# ESP32.net
KiCad netlist of a schematic drawn in Altium Designer
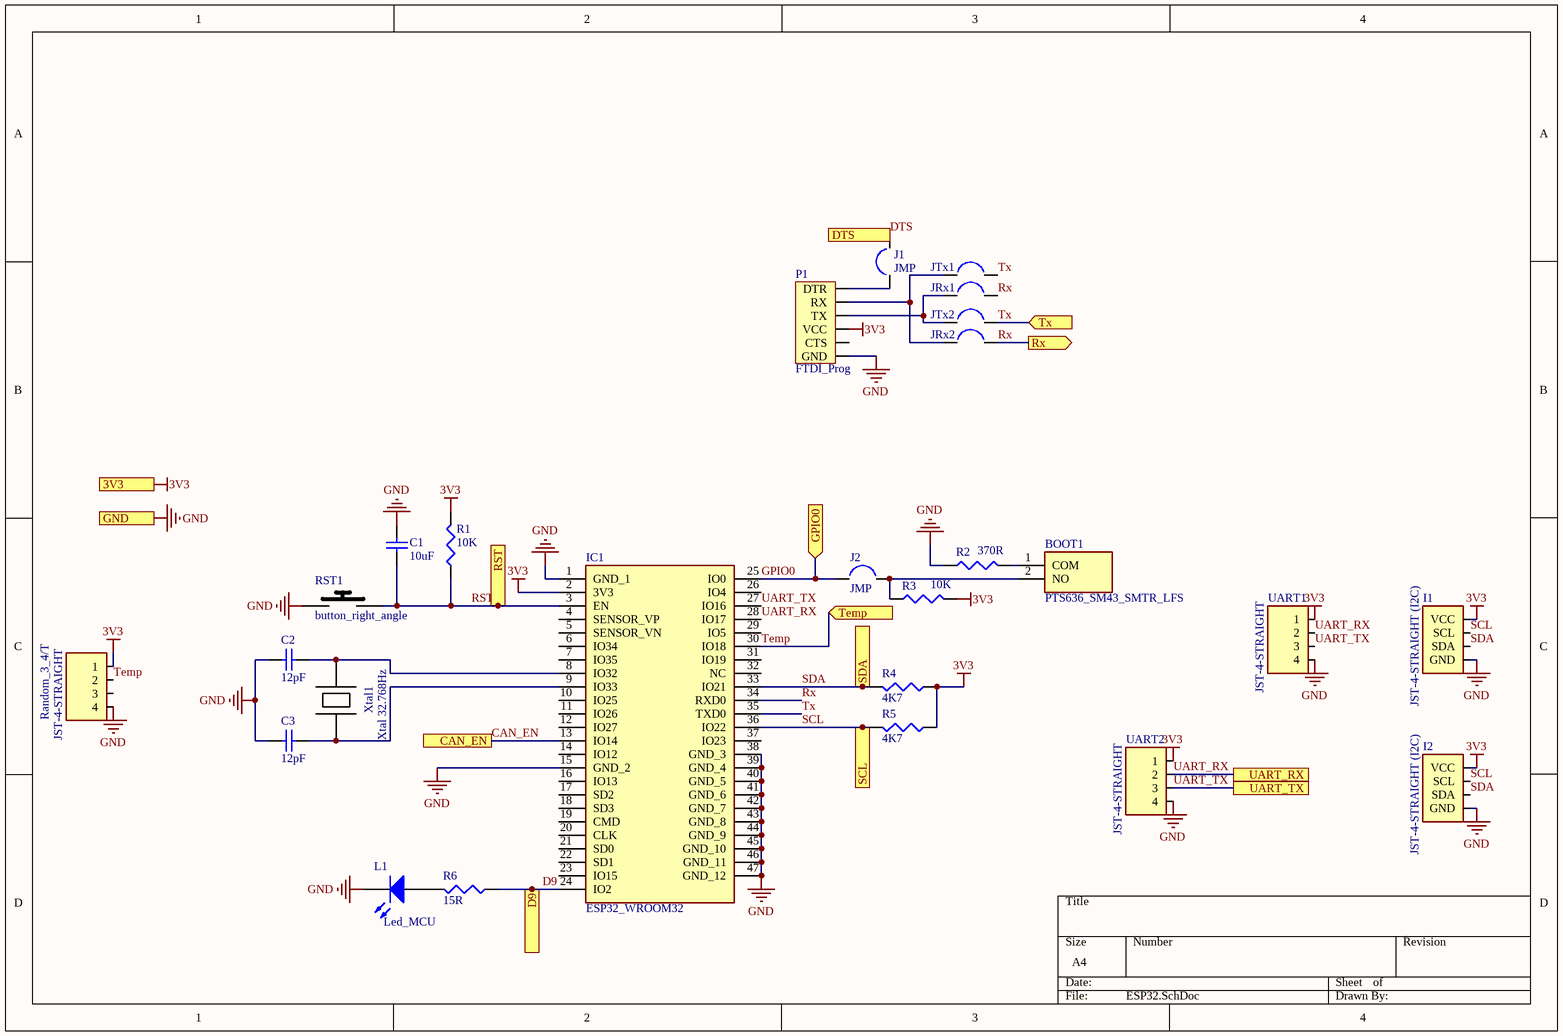
[diagram p0: ESP32.SchDoc]

(export (version "E")
  (design (tool "Eeschema 10.0.6"))
  (components
    (comp (ref "BOOT1")
      (value "PTS636_SM43_SMTR_LFS")
      (footprint "SamacSys:PTS636SM43SMTRLFS")
      (description "Switch")
      (fields
        (field (name "MANUFACTURER_PART_NUMBER") "PTS636 SM43 SMTR LFS")
        (field (name "MOUSER PART NUMBER") "611-PTS636SM43SMTRLF")
      )
      (libsource (lib "*") (part "PTS636_SM43_SMTR_LFS"))
    )
    (comp (ref "C1")
      (value "10uF")
      (footprint "1608[0603]")
      (description "Capacitor (Semiconductor SIM Model)")
      (fields (field (name "PUBLISHER") "Altium Limited"))
      (libsource (lib "Miscellaneous Devices") (part "Cap Semi"))
    )
    (comp (ref "C2")
      (value "12pF")
      (footprint "1608[0603]")
      (description "Capacitor (Semiconductor SIM Model)")
      (fields (field (name "PUBLISHER") "Altium Limited"))
      (libsource (lib "Miscellaneous Devices") (part "Cap Semi"))
    )
    (comp (ref "C3")
      (value "12pF")
      (footprint "1608[0603]")
      (description "Capacitor (Semiconductor SIM Model)")
      (fields (field (name "PUBLISHER") "Altium Limited"))
      (libsource (lib "Miscellaneous Devices") (part "Cap Semi"))
    )
    (comp (ref "I1")
      (value "JST-4-STRAIGHT (I2C)")
      (footprint "JST-4-STRAIGHT")
      (libsource (lib "SamacSys") (part "JST-4-STRAIGHT (I2C)"))
    )
    (comp (ref "I2")
      (value "JST-4-STRAIGHT (I2C)")
      (footprint "JST-4-STRAIGHT")
      (libsource (lib "SamacSys") (part "JST-4-STRAIGHT (I2C)"))
    )
    (comp (ref "IC1")
      (value "ESP32_WROOM32")
      (footprint "SamacSys:ESP32WROOM32")
      (description "Integrated Circuit")
      (fields (field (name "MANUFACTURER_PART_NUMBER") "ESP32 WROOM32"))
      (libsource (lib "SamacSys") (part "ESP32_WROOM32"))
    )
    (comp (ref "J1") (value "JMP") (footprint "Jumper") (libsource (lib "SamacSys") (part "JMP")))
    (comp (ref "J2") (value "JMP") (footprint "Jumper") (libsource (lib "SamacSys") (part "JMP")))
    (comp (ref "JRx1") (value "JMP") (footprint "Jumper") (libsource (lib "SamacSys") (part "JMP")))
    (comp (ref "JRx2") (value "JMP") (footprint "Jumper") (libsource (lib "SamacSys") (part "JMP")))
    (comp (ref "JTx1") (value "JMP") (footprint "Jumper") (libsource (lib "SamacSys") (part "JMP")))
    (comp (ref "JTx2") (value "JMP") (footprint "Jumper") (libsource (lib "SamacSys") (part "JMP")))
    (comp (ref "L1")
      (value "Led_MCU")
      (footprint "LED 0603")
      (description "Typical BLUE SiC LED")
      (fields (field (name "PUBLISHER") "Altium Limited"))
      (libsource (lib "Miscellaneous Devices") (part "LED3"))
    )
    (comp (ref "P1")
      (value "FTDI_Prog")
      (footprint "programer")
      (description "FTDI_programer FT232RL USB TO TTL")
      (libsource (lib "SamacSys") (part "Programer"))
    )
    (comp (ref "R1")
      (value "10K")
      (footprint "J1-0603")
      (description "Resistor")
      (fields (field (name "PUBLISHER") "Altium Limited"))
      (libsource (lib "Miscellaneous Devices") (part "Res3"))
    )
    (comp (ref "R2")
      (value "370R")
      (footprint "J1-0603")
      (description "Resistor")
      (fields (field (name "PUBLISHER") "Altium Limited"))
      (libsource (lib "Miscellaneous Devices") (part "Res3"))
    )
    (comp (ref "R3")
      (value "10K")
      (footprint "J1-0603")
      (description "Resistor")
      (fields (field (name "PUBLISHER") "Altium Limited"))
      (libsource (lib "Miscellaneous Devices") (part "Res3"))
    )
    (comp (ref "R4")
      (value "4K7")
      (footprint "J1-0603")
      (description "Resistor")
      (fields (field (name "PUBLISHER") "Altium Limited"))
      (libsource (lib "Miscellaneous Devices") (part "Res3"))
    )
    (comp (ref "R5")
      (value "4K7")
      (footprint "J1-0603")
      (description "Resistor")
      (fields (field (name "PUBLISHER") "Altium Limited"))
      (libsource (lib "Miscellaneous Devices") (part "Res3"))
    )
    (comp (ref "R6")
      (value "15R")
      (footprint "J1-0603")
      (description "Resistor")
      (fields (field (name "PUBLISHER") "Altium Limited"))
      (libsource (lib "Miscellaneous Devices") (part "Res3"))
    )
    (comp (ref "Random_3_4/T")
      (value "JST-4-STRAIGHT")
      (footprint "JST-4-STRAIGHT")
      (libsource (lib "SamacSys") (part "JST-4-STRAIGHT"))
    )
    (comp (ref "RST1")
      (value "button_right_angle")
      (footprint "1825027-8")
      (description "Switch")
      (fields
        (field (name "MANUFACTURER_PART_NUMBER") "1825027-8")
        (field (name "MOUSER PART NUMBER") "506-1825027-8")
      )
      (libsource (lib "SamacSys") (part "button_right_angle"))
    )
    (comp (ref "UART1")
      (value "JST-4-STRAIGHT")
      (footprint "JST-4-STRAIGHT")
      (libsource (lib "SamacSys") (part "JST-4-STRAIGHT"))
    )
    (comp (ref "UART2")
      (value "JST-4-STRAIGHT")
      (footprint "JST-4-STRAIGHT")
      (libsource (lib "SamacSys") (part "JST-4-STRAIGHT"))
    )
    (comp (ref "Xtal1")
      (value "Xtal 32.768Hz")
      (footprint "LFXTAL050789")
      (description "32.7680kHz")
      (libsource (lib "SamacSys") (part "Crystals WE-XTAL 32.7680kHz"))
    )
  )
  (nets
    (net (code "1") (name "/CAN_EN") (class "Default")
      (node (ref "IC1") (pin "13") (pinfunction "IO14_13") (pintype "passive"))
    )
    (net (code "2") (name "/D9") (class "Default")
      (node (ref "IC1") (pin "24") (pinfunction "IO2_24") (pintype "passive"))
      (node (ref "R6") (pin "1") (pinfunction "1_1") (pintype "passive"))
    )
    (net (code "3") (name "/DTS") (class "Default")
      (node (ref "J1") (pin "2") (pinfunction "2_2") (pintype "passive"))
    )
    (net (code "4") (name "/GPIO0") (class "Default")
      (node (ref "IC1") (pin "25") (pinfunction "IO0_25") (pintype "passive"))
      (node (ref "J2") (pin "1") (pinfunction "1_1") (pintype "passive"))
    )
    (net (code "5") (name "/RST") (class "Default")
      (node (ref "C1") (pin "1") (pinfunction "1_1") (pintype "passive"))
      (node (ref "IC1") (pin "3") (pinfunction "EN_3") (pintype "passive"))
      (node (ref "R1") (pin "1") (pinfunction "1_1") (pintype "passive"))
      (node (ref "RST1") (pin "2") (pinfunction "2_2") (pintype "passive"))
    )
    (net (code "6") (name "/Rx") (class "Default")
      (node (ref "IC1") (pin "34") (pinfunction "RXD0_34") (pintype "passive"))
      (node (ref "JRx1") (pin "2") (pinfunction "2_2") (pintype "passive"))
      (node (ref "JRx2") (pin "2") (pinfunction "2_2") (pintype "passive"))
    )
    (net (code "7") (name "/SCL") (class "Default")
      (node (ref "I1") (pin "2") (pinfunction "SCL_2") (pintype "passive"))
      (node (ref "I2") (pin "2") (pinfunction "SCL_2") (pintype "passive"))
      (node (ref "IC1") (pin "36") (pinfunction "IO22_36") (pintype "passive"))
      (node (ref "R5") (pin "2") (pinfunction "2_2") (pintype "passive"))
    )
    (net (code "8") (name "/SDA") (class "Default")
      (node (ref "I1") (pin "3") (pinfunction "SDA_3") (pintype "passive"))
      (node (ref "I2") (pin "3") (pinfunction "SDA_3") (pintype "passive"))
      (node (ref "IC1") (pin "33") (pinfunction "IO21_33") (pintype "passive"))
      (node (ref "R4") (pin "2") (pinfunction "2_2") (pintype "passive"))
    )
    (net (code "9") (name "/Temp") (class "Default")
      (node (ref "IC1") (pin "30") (pinfunction "IO18_30") (pintype "passive"))
      (node (ref "Random_3_4/T") (pin "2") (pinfunction "2_2") (pintype "passive"))
    )
    (net (code "10") (name "/Tx") (class "Default")
      (node (ref "IC1") (pin "35") (pinfunction "TXD0_35") (pintype "passive"))
      (node (ref "JTx1") (pin "2") (pinfunction "2_2") (pintype "passive"))
      (node (ref "JTx2") (pin "2") (pinfunction "2_2") (pintype "passive"))
    )
    (net (code "11") (name "/UART_RX") (class "Default")
      (node (ref "IC1") (pin "28") (pinfunction "IO17_28") (pintype "passive"))
      (node (ref "UART1") (pin "2") (pinfunction "2_2") (pintype "passive"))
      (node (ref "UART2") (pin "2") (pinfunction "2_2") (pintype "passive"))
    )
    (net (code "12") (name "/UART_TX") (class "Default")
      (node (ref "IC1") (pin "27") (pinfunction "IO16_27") (pintype "passive"))
      (node (ref "UART1") (pin "3") (pinfunction "3_3") (pintype "passive"))
      (node (ref "UART2") (pin "3") (pinfunction "3_3") (pintype "passive"))
    )
    (net (code "13") (name "3V3") (class "Default")
      (node (ref "I1") (pin "1") (pinfunction "VCC_1") (pintype "passive"))
      (node (ref "I2") (pin "1") (pinfunction "VCC_1") (pintype "passive"))
      (node (ref "IC1") (pin "2") (pinfunction "3V3_2") (pintype "passive"))
      (node (ref "P1") (pin "4") (pinfunction "VCC_4") (pintype "passive"))
      (node (ref "R1") (pin "2") (pinfunction "2_2") (pintype "passive"))
      (node (ref "R3") (pin "2") (pinfunction "2_2") (pintype "passive"))
      (node (ref "R4") (pin "1") (pinfunction "1_1") (pintype "passive"))
      (node (ref "R5") (pin "1") (pinfunction "1_1") (pintype "passive"))
      (node (ref "Random_3_4/T") (pin "1") (pinfunction "1_1") (pintype "passive"))
      (node (ref "UART1") (pin "1") (pinfunction "1_1") (pintype "passive"))
      (node (ref "UART2") (pin "1") (pinfunction "1_1") (pintype "passive"))
    )
    (net (code "14") (name "GND") (class "Default")
      (node (ref "C1") (pin "2") (pinfunction "2_2") (pintype "passive"))
      (node (ref "C2") (pin "2") (pinfunction "2_2") (pintype "passive"))
      (node (ref "C3") (pin "2") (pinfunction "2_2") (pintype "passive"))
      (node (ref "I1") (pin "4") (pinfunction "GND_4") (pintype "passive"))
      (node (ref "I2") (pin "4") (pinfunction "GND_4") (pintype "passive"))
      (node (ref "IC1") (pin "1") (pinfunction "GND_1_1") (pintype "passive"))
      (node (ref "IC1") (pin "15") (pinfunction "GND_2_15") (pintype "passive"))
      (node (ref "IC1") (pin "38") (pinfunction "GND_3_38") (pintype "passive"))
      (node (ref "IC1") (pin "39") (pinfunction "GND_4_39") (pintype "passive"))
      (node (ref "IC1") (pin "40") (pinfunction "GND_5_40") (pintype "passive"))
      (node (ref "IC1") (pin "41") (pinfunction "GND_6_41") (pintype "passive"))
      (node (ref "IC1") (pin "42") (pinfunction "GND_7_42") (pintype "passive"))
      (node (ref "IC1") (pin "43") (pinfunction "GND_8_43") (pintype "passive"))
      (node (ref "IC1") (pin "44") (pinfunction "GND_9_44") (pintype "passive"))
      (node (ref "IC1") (pin "45") (pinfunction "GND_10_45") (pintype "passive"))
      (node (ref "IC1") (pin "46") (pinfunction "GND_11_46") (pintype "passive"))
      (node (ref "IC1") (pin "47") (pinfunction "GND_12_47") (pintype "passive"))
      (node (ref "L1") (pin "2") (pinfunction "K_2") (pintype "passive"))
      (node (ref "P1") (pin "6") (pinfunction "GND_6") (pintype "passive"))
      (node (ref "R2") (pin "1") (pinfunction "1_1") (pintype "passive"))
      (node (ref "RST1") (pin "1") (pinfunction "1_1") (pintype "passive"))
      (node (ref "Random_3_4/T") (pin "4") (pinfunction "4_4") (pintype "passive"))
      (node (ref "UART1") (pin "4") (pinfunction "4_4") (pintype "passive"))
      (node (ref "UART2") (pin "4") (pinfunction "4_4") (pintype "passive"))
    )
    (net (code "15") (name "Net-(BOOT1-COM)") (class "Default")
      (node (ref "BOOT1") (pin "1") (pinfunction "COM_1") (pintype "passive"))
      (node (ref "R2") (pin "2") (pinfunction "2_2") (pintype "passive"))
    )
    (net (code "16") (name "Net-(BOOT1-NO)") (class "Default")
      (node (ref "BOOT1") (pin "2") (pinfunction "NO_2") (pintype "passive"))
      (node (ref "J2") (pin "2") (pinfunction "2_2") (pintype "passive"))
      (node (ref "R3") (pin "1") (pinfunction "1_1") (pintype "passive"))
    )
    (net (code "17") (name "Net-(IC1-IO32)") (class "Default")
      (node (ref "C2") (pin "1") (pinfunction "1_1") (pintype "passive"))
      (node (ref "IC1") (pin "8") (pinfunction "IO32_8") (pintype "passive"))
      (node (ref "Xtal1") (pin "2") (pinfunction "2_2") (pintype "passive"))
    )
    (net (code "18") (name "Net-(IC1-IO33)") (class "Default")
      (node (ref "C3") (pin "1") (pinfunction "1_1") (pintype "passive"))
      (node (ref "IC1") (pin "9") (pinfunction "IO33_9") (pintype "passive"))
      (node (ref "Xtal1") (pin "1") (pinfunction "1_1") (pintype "passive"))
    )
    (net (code "19") (name "Net-(L1-A)") (class "Default")
      (node (ref "L1") (pin "1") (pinfunction "A_1") (pintype "passive"))
      (node (ref "R6") (pin "2") (pinfunction "2_2") (pintype "passive"))
    )
    (net (code "20") (name "Net-(P1-DTR)") (class "Default")
      (node (ref "J1") (pin "1") (pinfunction "1_1") (pintype "passive"))
      (node (ref "P1") (pin "1") (pinfunction "DTR_1") (pintype "passive"))
    )
    (net (code "21") (name "Net-(P1-RX)") (class "Default")
      (node (ref "JRx2") (pin "1") (pinfunction "1_1") (pintype "passive"))
      (node (ref "JTx1") (pin "1") (pinfunction "1_1") (pintype "passive"))
      (node (ref "P1") (pin "2") (pinfunction "RX_2") (pintype "passive"))
    )
    (net (code "22") (name "Net-(P1-TX)") (class "Default")
      (node (ref "JRx1") (pin "1") (pinfunction "1_1") (pintype "passive"))
      (node (ref "JTx2") (pin "1") (pinfunction "1_1") (pintype "passive"))
      (node (ref "P1") (pin "3") (pinfunction "TX_3") (pintype "passive"))
    )
    (net (code "23") (name "unconnected-(IC1-CLK-Pad20)") (class "Default")
      (node (ref "IC1") (pin "20") (pinfunction "CLK_20") (pintype "passive"))
    )
    (net (code "24") (name "unconnected-(IC1-CMD-Pad19)") (class "Default")
      (node (ref "IC1") (pin "19") (pinfunction "CMD_19") (pintype "passive"))
    )
    (net (code "25") (name "unconnected-(IC1-IO4-Pad26)") (class "Default")
      (node (ref "IC1") (pin "26") (pinfunction "IO4_26") (pintype "passive"))
    )
    (net (code "26") (name "unconnected-(IC1-IO5-Pad29)") (class "Default")
      (node (ref "IC1") (pin "29") (pinfunction "IO5_29") (pintype "passive"))
    )
    (net (code "27") (name "unconnected-(IC1-IO12-Pad14)") (class "Default")
      (node (ref "IC1") (pin "14") (pinfunction "IO12_14") (pintype "passive"))
    )
    (net (code "28") (name "unconnected-(IC1-IO13-Pad16)") (class "Default")
      (node (ref "IC1") (pin "16") (pinfunction "IO13_16") (pintype "passive"))
    )
    (net (code "29") (name "unconnected-(IC1-IO15-Pad23)") (class "Default")
      (node (ref "IC1") (pin "23") (pinfunction "IO15_23") (pintype "passive"))
    )
    (net (code "30") (name "unconnected-(IC1-IO19-Pad31)") (class "Default")
      (node (ref "IC1") (pin "31") (pinfunction "IO19_31") (pintype "passive"))
    )
    (net (code "31") (name "unconnected-(IC1-IO23-Pad37)") (class "Default")
      (node (ref "IC1") (pin "37") (pinfunction "IO23_37") (pintype "passive"))
    )
    (net (code "32") (name "unconnected-(IC1-IO25-Pad10)") (class "Default")
      (node (ref "IC1") (pin "10") (pinfunction "IO25_10") (pintype "passive"))
    )
    (net (code "33") (name "unconnected-(IC1-IO26-Pad11)") (class "Default")
      (node (ref "IC1") (pin "11") (pinfunction "IO26_11") (pintype "passive"))
    )
    (net (code "34") (name "unconnected-(IC1-IO27-Pad12)") (class "Default")
      (node (ref "IC1") (pin "12") (pinfunction "IO27_12") (pintype "passive"))
    )
    (net (code "35") (name "unconnected-(IC1-IO34-Pad6)") (class "Default")
      (node (ref "IC1") (pin "6") (pinfunction "IO34_6") (pintype "passive"))
    )
    (net (code "36") (name "unconnected-(IC1-IO35-Pad7)") (class "Default")
      (node (ref "IC1") (pin "7") (pinfunction "IO35_7") (pintype "passive"))
    )
    (net (code "37") (name "unconnected-(IC1-NC-Pad32)") (class "Default")
      (node (ref "IC1") (pin "32") (pinfunction "NC_32") (pintype "passive"))
    )
    (net (code "38") (name "unconnected-(IC1-SD0-Pad21)") (class "Default")
      (node (ref "IC1") (pin "21") (pinfunction "SD0_21") (pintype "passive"))
    )
    (net (code "39") (name "unconnected-(IC1-SD1-Pad22)") (class "Default")
      (node (ref "IC1") (pin "22") (pinfunction "SD1_22") (pintype "passive"))
    )
    (net (code "40") (name "unconnected-(IC1-SD2-Pad17)") (class "Default")
      (node (ref "IC1") (pin "17") (pinfunction "SD2_17") (pintype "passive"))
    )
    (net (code "41") (name "unconnected-(IC1-SD3-Pad18)") (class "Default")
      (node (ref "IC1") (pin "18") (pinfunction "SD3_18") (pintype "passive"))
    )
    (net (code "42") (name "unconnected-(IC1-SENSOR_VN-Pad5)") (class "Default")
      (node (ref "IC1") (pin "5") (pinfunction "SENSOR_VN_5") (pintype "passive"))
    )
    (net (code "43") (name "unconnected-(IC1-SENSOR_VP-Pad4)") (class "Default")
      (node (ref "IC1") (pin "4") (pinfunction "SENSOR_VP_4") (pintype "passive"))
    )
    (net (code "44") (name "unconnected-(P1-CTS-Pad5)") (class "Default")
      (node (ref "P1") (pin "5") (pinfunction "CTS_5") (pintype "passive"))
    )
    (net (code "45") (name "unconnected-(Random_3_4/T-Pad3)") (class "Default")
      (node (ref "Random_3_4/T") (pin "3") (pinfunction "3_3") (pintype "passive"))
    )
  )
)
